# CM4_Conn.net
KiCad netlist of a schematic drawn in Altium Designer
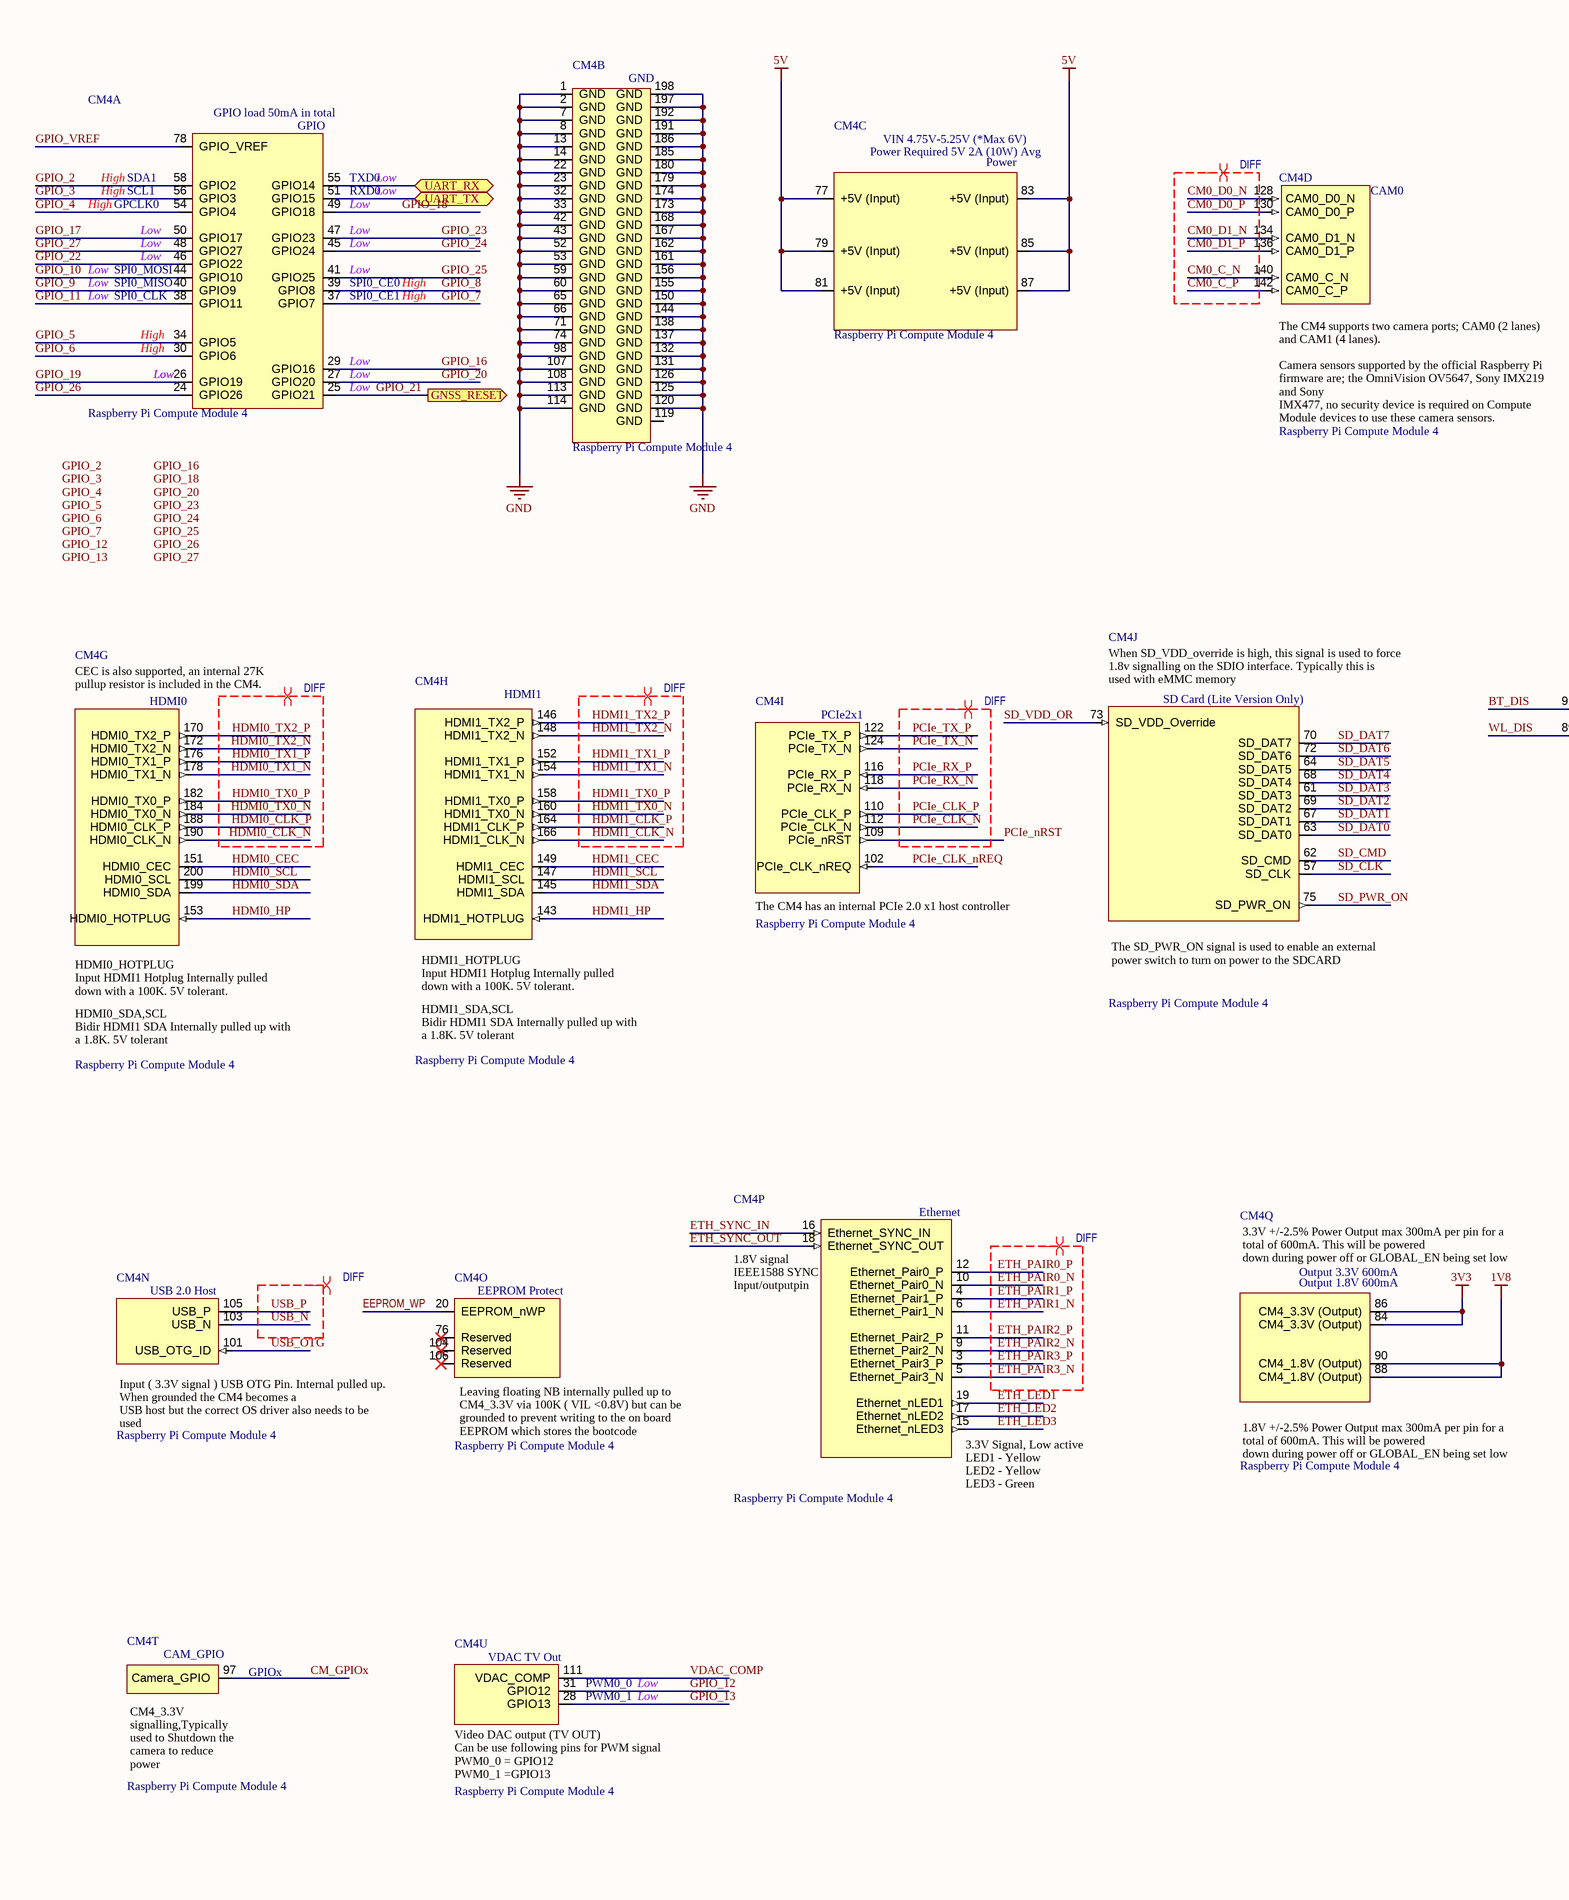
[diagram p0: CM4_Conn.SchDoc, left]
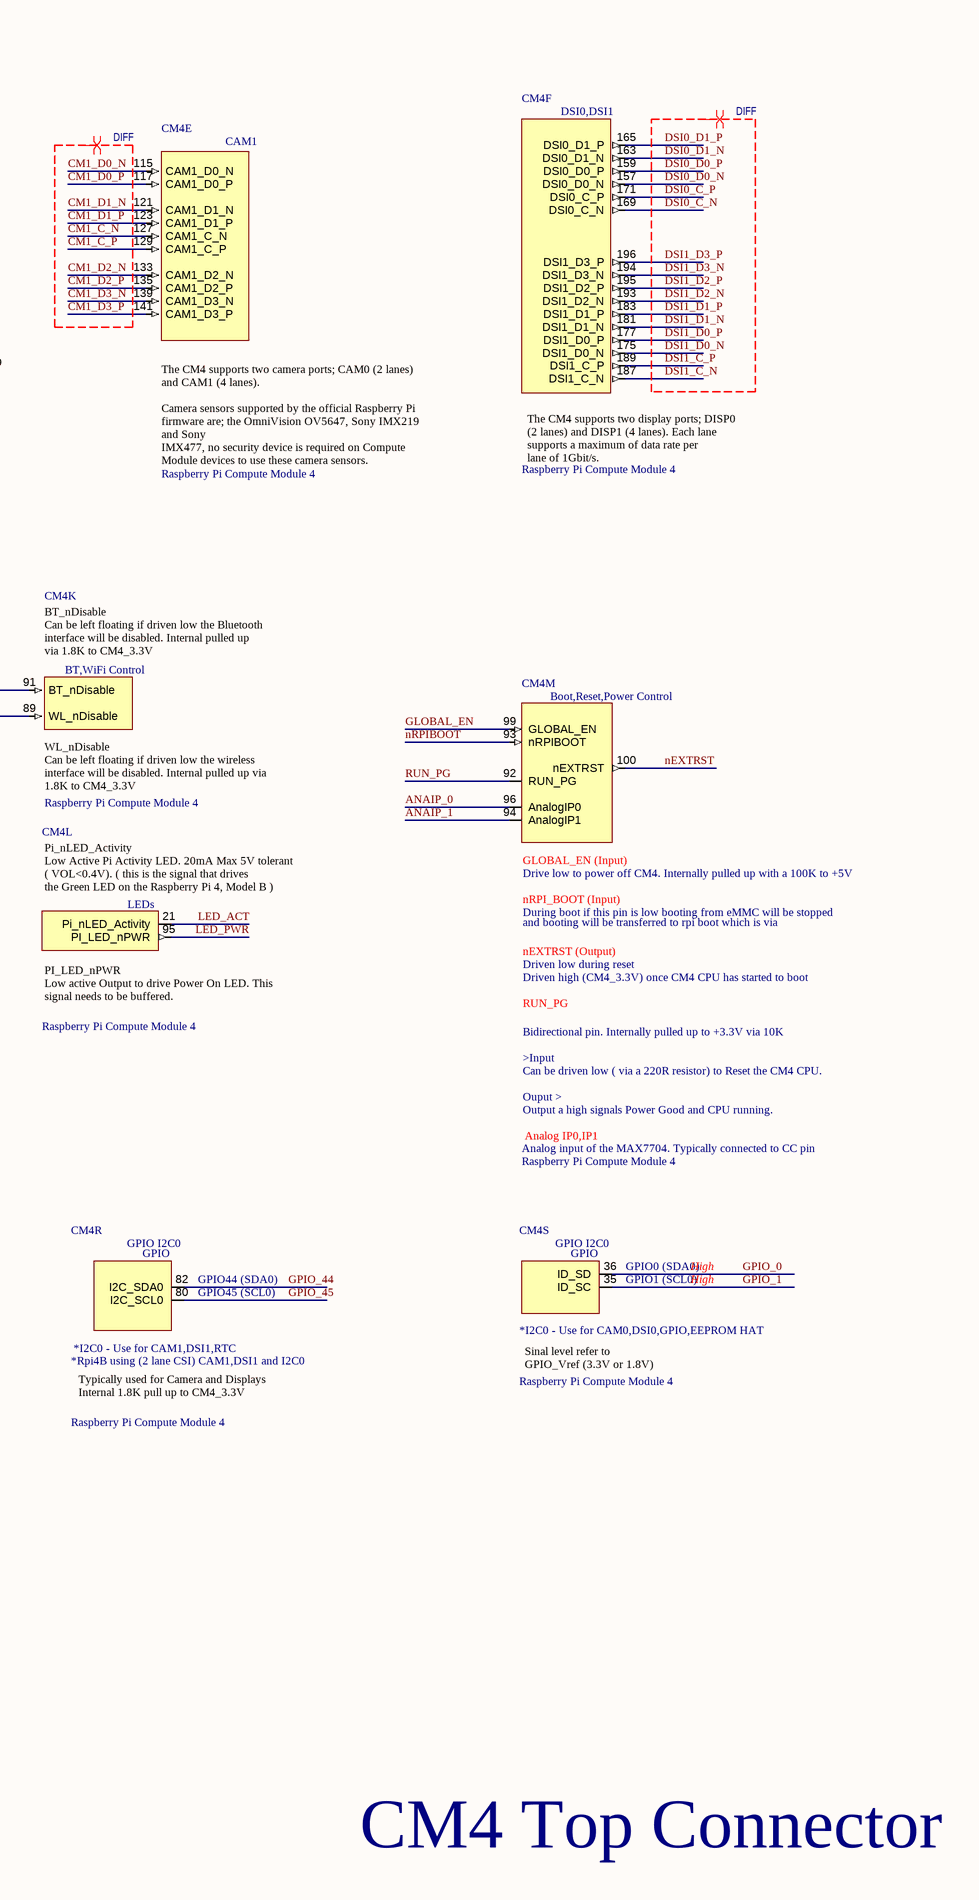
[diagram p1: CM4_Conn.SchDoc, right]

(export (version "E")
  (design (tool "Eeschema 10.0.6"))
  (components
    (comp (ref "CM4")
      (value "Raspberry Pi Compute Module 4")
      (footprint "CM4-F40C-100DS-0.4v_1.5mm_0mm")
      (description "Raspberry Pi Compute Module 4 by Amornthep Phunsin")
      (libsource (lib "CM4") (part "CM4"))
    )
  )
  (nets
    (net (code "1") (name "/ANAIP_0") (class "Default")
      (node (ref "CM4") (pin "96") (pinfunction "AnalogIP0_96") (pintype "passive"))
    )
    (net (code "2") (name "/ANAIP_1") (class "Default")
      (node (ref "CM4") (pin "94") (pinfunction "AnalogIP1_94") (pintype "passive"))
    )
    (net (code "3") (name "/BT_DIS") (class "Default")
      (node (ref "CM4") (pin "91") (pinfunction "BT_nDisable_91") (pintype "input"))
    )
    (net (code "4") (name "/CM0_C_N") (class "Default")
      (node (ref "CM4") (pin "140") (pinfunction "CAM0_C_N_140") (pintype "input"))
    )
    (net (code "5") (name "/CM0_C_P") (class "Default")
      (node (ref "CM4") (pin "142") (pinfunction "CAM0_C_P_142") (pintype "input"))
    )
    (net (code "6") (name "/CM0_D0_N") (class "Default")
      (node (ref "CM4") (pin "128") (pinfunction "CAM0_D0_N_128") (pintype "input"))
    )
    (net (code "7") (name "/CM0_D0_P") (class "Default")
      (node (ref "CM4") (pin "130") (pinfunction "CAM0_D0_P_130") (pintype "input"))
    )
    (net (code "8") (name "/CM0_D1_N") (class "Default")
      (node (ref "CM4") (pin "134") (pinfunction "CAM0_D1_N_134") (pintype "input"))
    )
    (net (code "9") (name "/CM0_D1_P") (class "Default")
      (node (ref "CM4") (pin "136") (pinfunction "CAM0_D1_P_136") (pintype "input"))
    )
    (net (code "10") (name "/CM1_C_N") (class "Default")
      (node (ref "CM4") (pin "127") (pinfunction "CAM1_C_N_127") (pintype "input"))
    )
    (net (code "11") (name "/CM1_C_P") (class "Default")
      (node (ref "CM4") (pin "129") (pinfunction "CAM1_C_P_129") (pintype "input"))
    )
    (net (code "12") (name "/CM1_D0_N") (class "Default")
      (node (ref "CM4") (pin "115") (pinfunction "CAM1_D0_N_115") (pintype "input"))
    )
    (net (code "13") (name "/CM1_D0_P") (class "Default")
      (node (ref "CM4") (pin "117") (pinfunction "CAM1_D0_P_117") (pintype "input"))
    )
    (net (code "14") (name "/CM1_D1_N") (class "Default")
      (node (ref "CM4") (pin "121") (pinfunction "CAM1_D1_N_121") (pintype "input"))
    )
    (net (code "15") (name "/CM1_D1_P") (class "Default")
      (node (ref "CM4") (pin "123") (pinfunction "CAM1_D1_P_123") (pintype "input"))
    )
    (net (code "16") (name "/CM1_D2_N") (class "Default")
      (node (ref "CM4") (pin "133") (pinfunction "CAM1_D2_N_133") (pintype "input"))
    )
    (net (code "17") (name "/CM1_D2_P") (class "Default")
      (node (ref "CM4") (pin "135") (pinfunction "CAM1_D2_P_135") (pintype "input"))
    )
    (net (code "18") (name "/CM1_D3_N") (class "Default")
      (node (ref "CM4") (pin "139") (pinfunction "CAM1_D3_N_139") (pintype "input"))
    )
    (net (code "19") (name "/CM1_D3_P") (class "Default")
      (node (ref "CM4") (pin "141") (pinfunction "CAM1_D3_P_141") (pintype "input"))
    )
    (net (code "20") (name "/CM_GPIOx") (class "Default")
      (node (ref "CM4") (pin "97") (pinfunction "Camera_GPIO_97") (pintype "passive"))
    )
    (net (code "21") (name "/DSI0_C_N") (class "Default")
      (node (ref "CM4") (pin "169") (pinfunction "DSI0_C_N_169") (pintype "output"))
    )
    (net (code "22") (name "/DSI0_C_P") (class "Default")
      (node (ref "CM4") (pin "171") (pinfunction "DSI0_C_P_171") (pintype "output"))
    )
    (net (code "23") (name "/DSI0_D0_N") (class "Default")
      (node (ref "CM4") (pin "157") (pinfunction "DSI0_D0_N_157") (pintype "output"))
    )
    (net (code "24") (name "/DSI0_D0_P") (class "Default")
      (node (ref "CM4") (pin "159") (pinfunction "DSI0_D0_P_159") (pintype "output"))
    )
    (net (code "25") (name "/DSI0_D1_N") (class "Default")
      (node (ref "CM4") (pin "163") (pinfunction "DSI0_D1_N_163") (pintype "output"))
    )
    (net (code "26") (name "/DSI0_D1_P") (class "Default")
      (node (ref "CM4") (pin "165") (pinfunction "DSI0_D1_P_165") (pintype "output"))
    )
    (net (code "27") (name "/DSI1_C_N") (class "Default")
      (node (ref "CM4") (pin "187") (pinfunction "DSI1_C_N_187") (pintype "output"))
    )
    (net (code "28") (name "/DSI1_C_P") (class "Default")
      (node (ref "CM4") (pin "189") (pinfunction "DSI1_C_P_189") (pintype "output"))
    )
    (net (code "29") (name "/DSI1_D0_N") (class "Default")
      (node (ref "CM4") (pin "175") (pinfunction "DSI1_D0_N_175") (pintype "output"))
    )
    (net (code "30") (name "/DSI1_D0_P") (class "Default")
      (node (ref "CM4") (pin "177") (pinfunction "DSI1_D0_P_177") (pintype "output"))
    )
    (net (code "31") (name "/DSI1_D1_N") (class "Default")
      (node (ref "CM4") (pin "181") (pinfunction "DSI1_D1_N_181") (pintype "output"))
    )
    (net (code "32") (name "/DSI1_D1_P") (class "Default")
      (node (ref "CM4") (pin "183") (pinfunction "DSI1_D1_P_183") (pintype "output"))
    )
    (net (code "33") (name "/DSI1_D2_N") (class "Default")
      (node (ref "CM4") (pin "193") (pinfunction "DSI1_D2_N_193") (pintype "output"))
    )
    (net (code "34") (name "/DSI1_D2_P") (class "Default")
      (node (ref "CM4") (pin "195") (pinfunction "DSI1_D2_P_195") (pintype "output"))
    )
    (net (code "35") (name "/DSI1_D3_N") (class "Default")
      (node (ref "CM4") (pin "194") (pinfunction "DSI1_D3_N_194") (pintype "output"))
    )
    (net (code "36") (name "/DSI1_D3_P") (class "Default")
      (node (ref "CM4") (pin "196") (pinfunction "DSI1_D3_P_196") (pintype "output"))
    )
    (net (code "37") (name "/EEPROM_WP") (class "Default")
      (node (ref "CM4") (pin "20") (pinfunction "EEPROM_nWP_20") (pintype "passive"))
    )
    (net (code "38") (name "/ETH_LED1") (class "Default")
      (node (ref "CM4") (pin "19") (pinfunction "Ethernet_nLED1_19") (pintype "output"))
    )
    (net (code "39") (name "/ETH_LED2") (class "Default")
      (node (ref "CM4") (pin "17") (pinfunction "Ethernet_nLED2_17") (pintype "output"))
    )
    (net (code "40") (name "/ETH_LED3") (class "Default")
      (node (ref "CM4") (pin "15") (pinfunction "Ethernet_nLED3_15") (pintype "output"))
    )
    (net (code "41") (name "/ETH_PAIR0_N") (class "Default")
      (node (ref "CM4") (pin "10") (pinfunction "Ethernet_Pair0_N_10") (pintype "passive"))
    )
    (net (code "42") (name "/ETH_PAIR0_P") (class "Default")
      (node (ref "CM4") (pin "12") (pinfunction "Ethernet_Pair0_P_12") (pintype "passive"))
    )
    (net (code "43") (name "/ETH_PAIR1_N") (class "Default")
      (node (ref "CM4") (pin "6") (pinfunction "Ethernet_Pair1_N_6") (pintype "passive"))
    )
    (net (code "44") (name "/ETH_PAIR1_P") (class "Default")
      (node (ref "CM4") (pin "4") (pinfunction "Ethernet_Pair1_P_4") (pintype "passive"))
    )
    (net (code "45") (name "/ETH_PAIR2_N") (class "Default")
      (node (ref "CM4") (pin "9") (pinfunction "Ethernet_Pair2_N_9") (pintype "passive"))
    )
    (net (code "46") (name "/ETH_PAIR2_P") (class "Default")
      (node (ref "CM4") (pin "11") (pinfunction "Ethernet_Pair2_P_11") (pintype "passive"))
    )
    (net (code "47") (name "/ETH_PAIR3_N") (class "Default")
      (node (ref "CM4") (pin "5") (pinfunction "Ethernet_Pair3_N_5") (pintype "passive"))
    )
    (net (code "48") (name "/ETH_PAIR3_P") (class "Default")
      (node (ref "CM4") (pin "3") (pinfunction "Ethernet_Pair3_P_3") (pintype "passive"))
    )
    (net (code "49") (name "/ETH_SYNC_IN") (class "Default")
      (node (ref "CM4") (pin "16") (pinfunction "Ethernet_SYNC_IN_16") (pintype "input"))
    )
    (net (code "50") (name "/ETH_SYNC_OUT") (class "Default")
      (node (ref "CM4") (pin "18") (pinfunction "Ethernet_SYNC_OUT_18") (pintype "input"))
    )
    (net (code "51") (name "/GLOBAL_EN") (class "Default")
      (node (ref "CM4") (pin "99") (pinfunction "GLOBAL_EN_99") (pintype "input"))
    )
    (net (code "52") (name "/GPIO_0") (class "Default")
      (node (ref "CM4") (pin "36") (pinfunction "ID_SD_36") (pintype "passive"))
    )
    (net (code "53") (name "/GPIO_1") (class "Default")
      (node (ref "CM4") (pin "35") (pinfunction "ID_SC_35") (pintype "passive"))
    )
    (net (code "54") (name "/GPIO_2") (class "Default")
      (node (ref "CM4") (pin "58") (pinfunction "GPIO2_58") (pintype "passive"))
    )
    (net (code "55") (name "/GPIO_3") (class "Default")
      (node (ref "CM4") (pin "56") (pinfunction "GPIO3_56") (pintype "passive"))
    )
    (net (code "56") (name "/GPIO_4") (class "Default")
      (node (ref "CM4") (pin "54") (pinfunction "GPIO4_54") (pintype "passive"))
    )
    (net (code "57") (name "/GPIO_5") (class "Default")
      (node (ref "CM4") (pin "34") (pinfunction "GPIO5_34") (pintype "passive"))
    )
    (net (code "58") (name "/GPIO_6") (class "Default")
      (node (ref "CM4") (pin "30") (pinfunction "GPIO6_30") (pintype "passive"))
    )
    (net (code "59") (name "/GPIO_7") (class "Default")
      (node (ref "CM4") (pin "37") (pinfunction "GPIO7_37") (pintype "passive"))
    )
    (net (code "60") (name "/GPIO_8") (class "Default")
      (node (ref "CM4") (pin "39") (pinfunction "GPIO8_39") (pintype "passive"))
    )
    (net (code "61") (name "/GPIO_9") (class "Default")
      (node (ref "CM4") (pin "40") (pinfunction "GPIO9_40") (pintype "passive"))
    )
    (net (code "62") (name "/GPIO_10") (class "Default")
      (node (ref "CM4") (pin "44") (pinfunction "GPIO10_44") (pintype "passive"))
    )
    (net (code "63") (name "/GPIO_11") (class "Default")
      (node (ref "CM4") (pin "38") (pinfunction "GPIO11_38") (pintype "passive"))
    )
    (net (code "64") (name "/GPIO_12") (class "Default")
      (node (ref "CM4") (pin "31") (pinfunction "GPIO12_31") (pintype "passive"))
    )
    (net (code "65") (name "/GPIO_13") (class "Default")
      (node (ref "CM4") (pin "28") (pinfunction "GPIO13_28") (pintype "passive"))
    )
    (net (code "66") (name "/GPIO_16") (class "Default")
      (node (ref "CM4") (pin "29") (pinfunction "GPIO16_29") (pintype "passive"))
    )
    (net (code "67") (name "/GPIO_17") (class "Default")
      (node (ref "CM4") (pin "50") (pinfunction "GPIO17_50") (pintype "passive"))
    )
    (net (code "68") (name "/GPIO_18") (class "Default")
      (node (ref "CM4") (pin "49") (pinfunction "GPIO18_49") (pintype "passive"))
    )
    (net (code "69") (name "/GPIO_19") (class "Default")
      (node (ref "CM4") (pin "26") (pinfunction "GPIO19_26") (pintype "passive"))
    )
    (net (code "70") (name "/GPIO_20") (class "Default")
      (node (ref "CM4") (pin "27") (pinfunction "GPIO20_27") (pintype "passive"))
    )
    (net (code "71") (name "/GPIO_21") (class "Default")
      (node (ref "CM4") (pin "25") (pinfunction "GPIO21_25") (pintype "passive"))
    )
    (net (code "72") (name "/GPIO_22") (class "Default")
      (node (ref "CM4") (pin "46") (pinfunction "GPIO22_46") (pintype "passive"))
    )
    (net (code "73") (name "/GPIO_23") (class "Default")
      (node (ref "CM4") (pin "47") (pinfunction "GPIO23_47") (pintype "passive"))
    )
    (net (code "74") (name "/GPIO_24") (class "Default")
      (node (ref "CM4") (pin "45") (pinfunction "GPIO24_45") (pintype "passive"))
    )
    (net (code "75") (name "/GPIO_25") (class "Default")
      (node (ref "CM4") (pin "41") (pinfunction "GPIO25_41") (pintype "passive"))
    )
    (net (code "76") (name "/GPIO_26") (class "Default")
      (node (ref "CM4") (pin "24") (pinfunction "GPIO26_24") (pintype "passive"))
    )
    (net (code "77") (name "/GPIO_27") (class "Default")
      (node (ref "CM4") (pin "48") (pinfunction "GPIO27_48") (pintype "passive"))
    )
    (net (code "78") (name "/GPIO_44") (class "Default")
      (node (ref "CM4") (pin "82") (pinfunction "I2C_SDA0_82") (pintype "passive"))
    )
    (net (code "79") (name "/GPIO_45") (class "Default")
      (node (ref "CM4") (pin "80") (pinfunction "I2C_SCL0_80") (pintype "passive"))
    )
    (net (code "80") (name "/GPIO_VREF") (class "Default")
      (node (ref "CM4") (pin "78") (pinfunction "GPIO_VREF_78") (pintype "power_in"))
    )
    (net (code "81") (name "/HDMI0_CEC") (class "Default")
      (node (ref "CM4") (pin "151") (pinfunction "HDMI0_CEC_151") (pintype "open_collector"))
    )
    (net (code "82") (name "/HDMI0_CLK_N") (class "Default")
      (node (ref "CM4") (pin "190") (pinfunction "HDMI0_CLK_N_190") (pintype "output"))
    )
    (net (code "83") (name "/HDMI0_CLK_P") (class "Default")
      (node (ref "CM4") (pin "188") (pinfunction "HDMI0_CLK_P_188") (pintype "output"))
    )
    (net (code "84") (name "/HDMI0_HP") (class "Default")
      (node (ref "CM4") (pin "153") (pinfunction "HDMI0_HOTPLUG_153") (pintype "input"))
    )
    (net (code "85") (name "/HDMI0_SCL") (class "Default")
      (node (ref "CM4") (pin "200") (pinfunction "HDMI0_SCL_200") (pintype "open_collector"))
    )
    (net (code "86") (name "/HDMI0_SDA") (class "Default")
      (node (ref "CM4") (pin "199") (pinfunction "HDMI0_SDA_199") (pintype "bidirectional"))
    )
    (net (code "87") (name "/HDMI0_TX0_N") (class "Default")
      (node (ref "CM4") (pin "184") (pinfunction "HDMI0_TX0_N_184") (pintype "output"))
    )
    (net (code "88") (name "/HDMI0_TX0_P") (class "Default")
      (node (ref "CM4") (pin "182") (pinfunction "HDMI0_TX0_P_182") (pintype "output"))
    )
    (net (code "89") (name "/HDMI0_TX1_N") (class "Default")
      (node (ref "CM4") (pin "178") (pinfunction "HDMI0_TX1_N_178") (pintype "output"))
    )
    (net (code "90") (name "/HDMI0_TX1_P") (class "Default")
      (node (ref "CM4") (pin "176") (pinfunction "HDMI0_TX1_P_176") (pintype "output"))
    )
    (net (code "91") (name "/HDMI0_TX2_N") (class "Default")
      (node (ref "CM4") (pin "172") (pinfunction "HDMI0_TX2_N_172") (pintype "output"))
    )
    (net (code "92") (name "/HDMI0_TX2_P") (class "Default")
      (node (ref "CM4") (pin "170") (pinfunction "HDMI0_TX2_P_170") (pintype "output"))
    )
    (net (code "93") (name "/HDMI1_CEC") (class "Default")
      (node (ref "CM4") (pin "149") (pinfunction "HDMI1_CEC_149") (pintype "open_collector"))
    )
    (net (code "94") (name "/HDMI1_CLK_N") (class "Default")
      (node (ref "CM4") (pin "166") (pinfunction "HDMI1_CLK_N_166") (pintype "output"))
    )
    (net (code "95") (name "/HDMI1_CLK_P") (class "Default")
      (node (ref "CM4") (pin "164") (pinfunction "HDMI1_CLK_P_164") (pintype "output"))
    )
    (net (code "96") (name "/HDMI1_HP") (class "Default")
      (node (ref "CM4") (pin "143") (pinfunction "HDMI1_HOTPLUG_143") (pintype "input"))
    )
    (net (code "97") (name "/HDMI1_SCL") (class "Default")
      (node (ref "CM4") (pin "147") (pinfunction "HDMI1_SCL_147") (pintype "open_collector"))
    )
    (net (code "98") (name "/HDMI1_SDA") (class "Default")
      (node (ref "CM4") (pin "145") (pinfunction "HDMI1_SDA_145") (pintype "bidirectional"))
    )
    (net (code "99") (name "/HDMI1_TX0_N") (class "Default")
      (node (ref "CM4") (pin "160") (pinfunction "HDMI1_TX0_N_160") (pintype "output"))
    )
    (net (code "100") (name "/HDMI1_TX0_P") (class "Default")
      (node (ref "CM4") (pin "158") (pinfunction "HDMI1_TX0_P_158") (pintype "output"))
    )
    (net (code "101") (name "/HDMI1_TX1_N") (class "Default")
      (node (ref "CM4") (pin "154") (pinfunction "HDMI1_TX1_N_154") (pintype "output"))
    )
    (net (code "102") (name "/HDMI1_TX1_P") (class "Default")
      (node (ref "CM4") (pin "152") (pinfunction "HDMI1_TX1_P_152") (pintype "output"))
    )
    (net (code "103") (name "/HDMI1_TX2_N") (class "Default")
      (node (ref "CM4") (pin "148") (pinfunction "HDMI1_TX2_N_148") (pintype "output"))
    )
    (net (code "104") (name "/HDMI1_TX2_P") (class "Default")
      (node (ref "CM4") (pin "146") (pinfunction "HDMI1_TX2_P_146") (pintype "output"))
    )
    (net (code "105") (name "/LED_ACT") (class "Default")
      (node (ref "CM4") (pin "21") (pinfunction "Pi_nLED_Activity_21") (pintype "open_collector"))
    )
    (net (code "106") (name "/LED_PWR") (class "Default")
      (node (ref "CM4") (pin "95") (pinfunction "PI_LED_nPWR_95") (pintype "output"))
    )
    (net (code "107") (name "/PCIe_CLK_N") (class "Default")
      (node (ref "CM4") (pin "112") (pinfunction "PCIe_CLK_N_112") (pintype "output"))
    )
    (net (code "108") (name "/PCIe_CLK_P") (class "Default")
      (node (ref "CM4") (pin "110") (pinfunction "PCIe_CLK_P_110") (pintype "output"))
    )
    (net (code "109") (name "/PCIe_CLK_nREQ") (class "Default")
      (node (ref "CM4") (pin "102") (pinfunction "PCIe_CLK_nREQ_102") (pintype "input"))
    )
    (net (code "110") (name "/PCIe_RX_N") (class "Default")
      (node (ref "CM4") (pin "118") (pinfunction "PCIe_RX_N_118") (pintype "input"))
    )
    (net (code "111") (name "/PCIe_RX_P") (class "Default")
      (node (ref "CM4") (pin "116") (pinfunction "PCIe_RX_P_116") (pintype "input"))
    )
    (net (code "112") (name "/PCIe_TX_N") (class "Default")
      (node (ref "CM4") (pin "124") (pinfunction "PCIe_TX_N_124") (pintype "output"))
    )
    (net (code "113") (name "/PCIe_TX_P") (class "Default")
      (node (ref "CM4") (pin "122") (pinfunction "PCIe_TX_P_122") (pintype "output"))
    )
    (net (code "114") (name "/PCIe_nRST") (class "Default")
      (node (ref "CM4") (pin "109") (pinfunction "PCIe_nRST_109") (pintype "output"))
    )
    (net (code "115") (name "/RUN_PG") (class "Default")
      (node (ref "CM4") (pin "92") (pinfunction "RUN_PG_92") (pintype "passive"))
    )
    (net (code "116") (name "/SD_CLK") (class "Default")
      (node (ref "CM4") (pin "57") (pinfunction "SD_CLK_57") (pintype "passive"))
    )
    (net (code "117") (name "/SD_CMD") (class "Default")
      (node (ref "CM4") (pin "62") (pinfunction "SD_CMD_62") (pintype "passive"))
    )
    (net (code "118") (name "/SD_DAT0") (class "Default")
      (node (ref "CM4") (pin "63") (pinfunction "SD_DAT0_63") (pintype "passive"))
    )
    (net (code "119") (name "/SD_DAT1") (class "Default")
      (node (ref "CM4") (pin "67") (pinfunction "SD_DAT1_67") (pintype "passive"))
    )
    (net (code "120") (name "/SD_DAT2") (class "Default")
      (node (ref "CM4") (pin "69") (pinfunction "SD_DAT2_69") (pintype "passive"))
    )
    (net (code "121") (name "/SD_DAT3") (class "Default")
      (node (ref "CM4") (pin "61") (pinfunction "SD_DAT3_61") (pintype "passive"))
    )
    (net (code "122") (name "/SD_DAT4") (class "Default")
      (node (ref "CM4") (pin "68") (pinfunction "SD_DAT4_68") (pintype "passive"))
    )
    (net (code "123") (name "/SD_DAT5") (class "Default")
      (node (ref "CM4") (pin "64") (pinfunction "SD_DAT5_64") (pintype "passive"))
    )
    (net (code "124") (name "/SD_DAT6") (class "Default")
      (node (ref "CM4") (pin "72") (pinfunction "SD_DAT6_72") (pintype "passive"))
    )
    (net (code "125") (name "/SD_DAT7") (class "Default")
      (node (ref "CM4") (pin "70") (pinfunction "SD_DAT7_70") (pintype "passive"))
    )
    (net (code "126") (name "/SD_PWR_ON") (class "Default")
      (node (ref "CM4") (pin "75") (pinfunction "SD_PWR_ON_75") (pintype "output"))
    )
    (net (code "127") (name "/SD_VDD_OR") (class "Default")
      (node (ref "CM4") (pin "73") (pinfunction "SD_VDD_Override_73") (pintype "input"))
    )
    (net (code "128") (name "/UART_RX") (class "Default")
      (node (ref "CM4") (pin "55") (pinfunction "GPIO14_55") (pintype "passive"))
    )
    (net (code "129") (name "/UART_TX") (class "Default")
      (node (ref "CM4") (pin "51") (pinfunction "GPIO15_51") (pintype "passive"))
    )
    (net (code "130") (name "/USB_N") (class "Default")
      (node (ref "CM4") (pin "103") (pinfunction "USB_N_103") (pintype "passive"))
    )
    (net (code "131") (name "/USB_OTG") (class "Default")
      (node (ref "CM4") (pin "101") (pinfunction "USB_OTG_ID_101") (pintype "input"))
    )
    (net (code "132") (name "/USB_P") (class "Default")
      (node (ref "CM4") (pin "105") (pinfunction "USB_P_105") (pintype "passive"))
    )
    (net (code "133") (name "/VDAC_COMP") (class "Default")
      (node (ref "CM4") (pin "111") (pinfunction "VDAC_COMP_111") (pintype "passive"))
    )
    (net (code "134") (name "/WL_DIS") (class "Default")
      (node (ref "CM4") (pin "89") (pinfunction "WL_nDisable_89") (pintype "input"))
    )
    (net (code "135") (name "/nEXTRST") (class "Default")
      (node (ref "CM4") (pin "100") (pinfunction "nEXTRST_100") (pintype "output"))
    )
    (net (code "136") (name "/nRPIBOOT") (class "Default")
      (node (ref "CM4") (pin "93") (pinfunction "nRPIBOOT_93") (pintype "input"))
    )
    (net (code "137") (name "1V8") (class "Default")
      (node (ref "CM4") (pin "88") (pinfunction "CM4_1.8V_(Output)_88") (pintype "power_in"))
      (node (ref "CM4") (pin "90") (pinfunction "CM4_1.8V_(Output)_90") (pintype "power_in"))
    )
    (net (code "138") (name "3V3") (class "Default")
      (node (ref "CM4") (pin "84") (pinfunction "CM4_3.3V_(Output)_84") (pintype "power_in"))
      (node (ref "CM4") (pin "86") (pinfunction "CM4_3.3V_(Output)_86") (pintype "power_in"))
    )
    (net (code "139") (name "5V") (class "Default")
      (node (ref "CM4") (pin "77") (pinfunction "+5V_(Input)_77") (pintype "power_in"))
      (node (ref "CM4") (pin "79") (pinfunction "+5V_(Input)_79") (pintype "power_in"))
      (node (ref "CM4") (pin "81") (pinfunction "+5V_(Input)_81") (pintype "power_in"))
      (node (ref "CM4") (pin "83") (pinfunction "+5V_(Input)_83") (pintype "power_in"))
      (node (ref "CM4") (pin "85") (pinfunction "+5V_(Input)_85") (pintype "power_in"))
      (node (ref "CM4") (pin "87") (pinfunction "+5V_(Input)_87") (pintype "power_in"))
    )
    (net (code "140") (name "GND") (class "Default")
      (node (ref "CM4") (pin "1") (pinfunction "GND_1") (pintype "power_in"))
      (node (ref "CM4") (pin "107") (pinfunction "GND_107") (pintype "power_in"))
      (node (ref "CM4") (pin "108") (pinfunction "GND_108") (pintype "power_in"))
      (node (ref "CM4") (pin "113") (pinfunction "GND_113") (pintype "power_in"))
      (node (ref "CM4") (pin "114") (pinfunction "GND_114") (pintype "power_in"))
      (node (ref "CM4") (pin "120") (pinfunction "GND_120") (pintype "power_in"))
      (node (ref "CM4") (pin "125") (pinfunction "GND_125") (pintype "power_in"))
      (node (ref "CM4") (pin "126") (pinfunction "GND_126") (pintype "power_in"))
      (node (ref "CM4") (pin "13") (pinfunction "GND_13") (pintype "power_in"))
      (node (ref "CM4") (pin "131") (pinfunction "GND_131") (pintype "power_in"))
      (node (ref "CM4") (pin "132") (pinfunction "GND_132") (pintype "power_in"))
      (node (ref "CM4") (pin "137") (pinfunction "GND_137") (pintype "power_in"))
      (node (ref "CM4") (pin "138") (pinfunction "GND_138") (pintype "power_in"))
      (node (ref "CM4") (pin "14") (pinfunction "GND_14") (pintype "power_in"))
      (node (ref "CM4") (pin "144") (pinfunction "GND_144") (pintype "power_in"))
      (node (ref "CM4") (pin "150") (pinfunction "GND_150") (pintype "power_in"))
      (node (ref "CM4") (pin "155") (pinfunction "GND_155") (pintype "power_in"))
      (node (ref "CM4") (pin "156") (pinfunction "GND_156") (pintype "power_in"))
      (node (ref "CM4") (pin "161") (pinfunction "GND_161") (pintype "power_in"))
      (node (ref "CM4") (pin "162") (pinfunction "GND_162") (pintype "power_in"))
      (node (ref "CM4") (pin "167") (pinfunction "GND_167") (pintype "power_in"))
      (node (ref "CM4") (pin "168") (pinfunction "GND_168") (pintype "power_in"))
      (node (ref "CM4") (pin "173") (pinfunction "GND_173") (pintype "power_in"))
      (node (ref "CM4") (pin "174") (pinfunction "GND_174") (pintype "power_in"))
      (node (ref "CM4") (pin "179") (pinfunction "GND_179") (pintype "power_in"))
      (node (ref "CM4") (pin "180") (pinfunction "GND_180") (pintype "power_in"))
      (node (ref "CM4") (pin "185") (pinfunction "GND_185") (pintype "power_in"))
      (node (ref "CM4") (pin "186") (pinfunction "GND_186") (pintype "power_in"))
      (node (ref "CM4") (pin "191") (pinfunction "GND_191") (pintype "power_in"))
      (node (ref "CM4") (pin "192") (pinfunction "GND_192") (pintype "power_in"))
      (node (ref "CM4") (pin "197") (pinfunction "GND_197") (pintype "power_in"))
      (node (ref "CM4") (pin "198") (pinfunction "GND_198") (pintype "power_in"))
      (node (ref "CM4") (pin "2") (pinfunction "GND_2") (pintype "power_in"))
      (node (ref "CM4") (pin "22") (pinfunction "GND_22") (pintype "power_in"))
      (node (ref "CM4") (pin "23") (pinfunction "GND_23") (pintype "power_in"))
      (node (ref "CM4") (pin "32") (pinfunction "GND_32") (pintype "power_in"))
      (node (ref "CM4") (pin "33") (pinfunction "GND_33") (pintype "power_in"))
      (node (ref "CM4") (pin "42") (pinfunction "GND_42") (pintype "power_in"))
      (node (ref "CM4") (pin "43") (pinfunction "GND_43") (pintype "power_in"))
      (node (ref "CM4") (pin "52") (pinfunction "GND_52") (pintype "power_in"))
      (node (ref "CM4") (pin "53") (pinfunction "GND_53") (pintype "power_in"))
      (node (ref "CM4") (pin "59") (pinfunction "GND_59") (pintype "power_in"))
      (node (ref "CM4") (pin "60") (pinfunction "GND_60") (pintype "power_in"))
      (node (ref "CM4") (pin "65") (pinfunction "GND_65") (pintype "power_in"))
      (node (ref "CM4") (pin "66") (pinfunction "GND_66") (pintype "power_in"))
      (node (ref "CM4") (pin "7") (pinfunction "GND_7") (pintype "power_in"))
      (node (ref "CM4") (pin "71") (pinfunction "GND_71") (pintype "power_in"))
      (node (ref "CM4") (pin "74") (pinfunction "GND_74") (pintype "power_in"))
      (node (ref "CM4") (pin "8") (pinfunction "GND_8") (pintype "power_in"))
      (node (ref "CM4") (pin "98") (pinfunction "GND_98") (pintype "power_in"))
    )
    (net (code "141") (name "unconnected-(CM4B-GND-Pad119)") (class "Default")
      (node (ref "CM4") (pin "119") (pinfunction "GND_119") (pintype "power_in"))
    )
    (net (code "142") (name "unconnected-(CM4O-Reserved-Pad76)") (class "Default")
      (node (ref "CM4") (pin "76") (pinfunction "Reserved_76") (pintype "passive+no_connect"))
    )
    (net (code "143") (name "unconnected-(CM4O-Reserved-Pad104)") (class "Default")
      (node (ref "CM4") (pin "104") (pinfunction "Reserved_104") (pintype "passive+no_connect"))
    )
    (net (code "144") (name "unconnected-(CM4O-Reserved-Pad106)") (class "Default")
      (node (ref "CM4") (pin "106") (pinfunction "Reserved_106") (pintype "passive+no_connect"))
    )
  )
)
